# mainboard.net
KiCad netlist of a schematic drawn in EAGLE
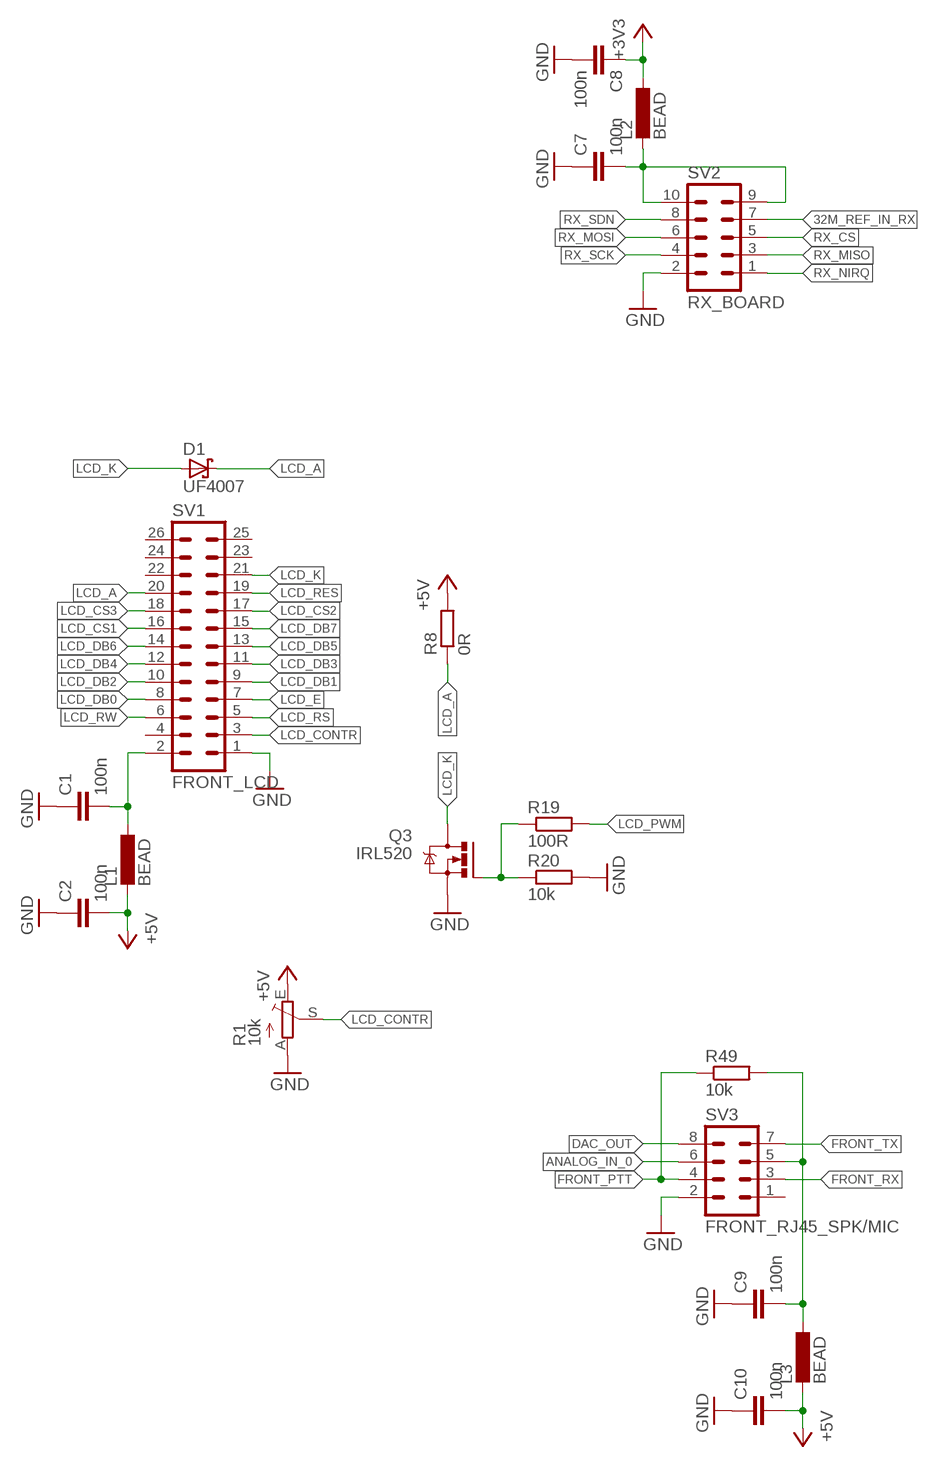
[diagram p0: schematic, sheet 1, part 1 of 3]
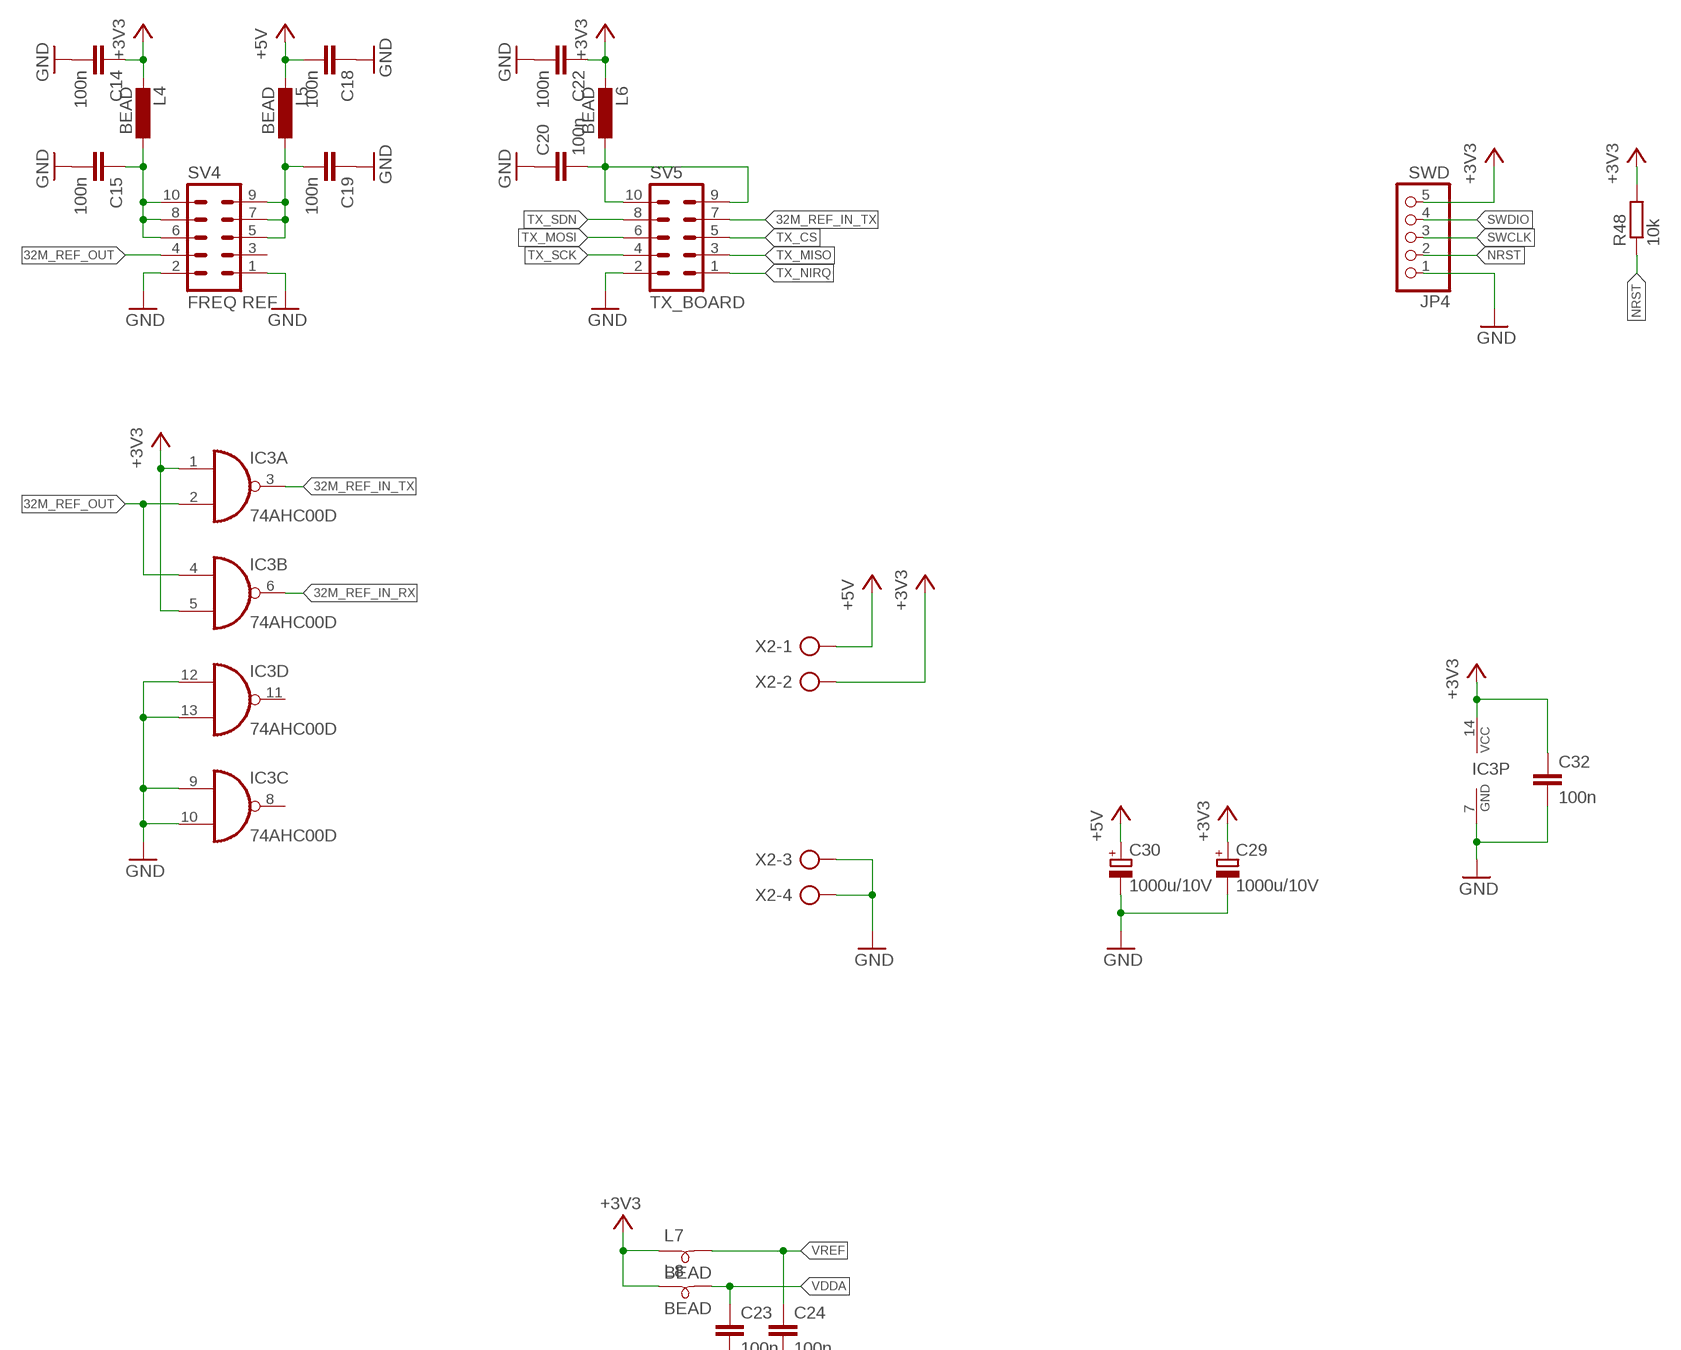
[diagram p1: schematic, sheet 1, part 2 of 3]
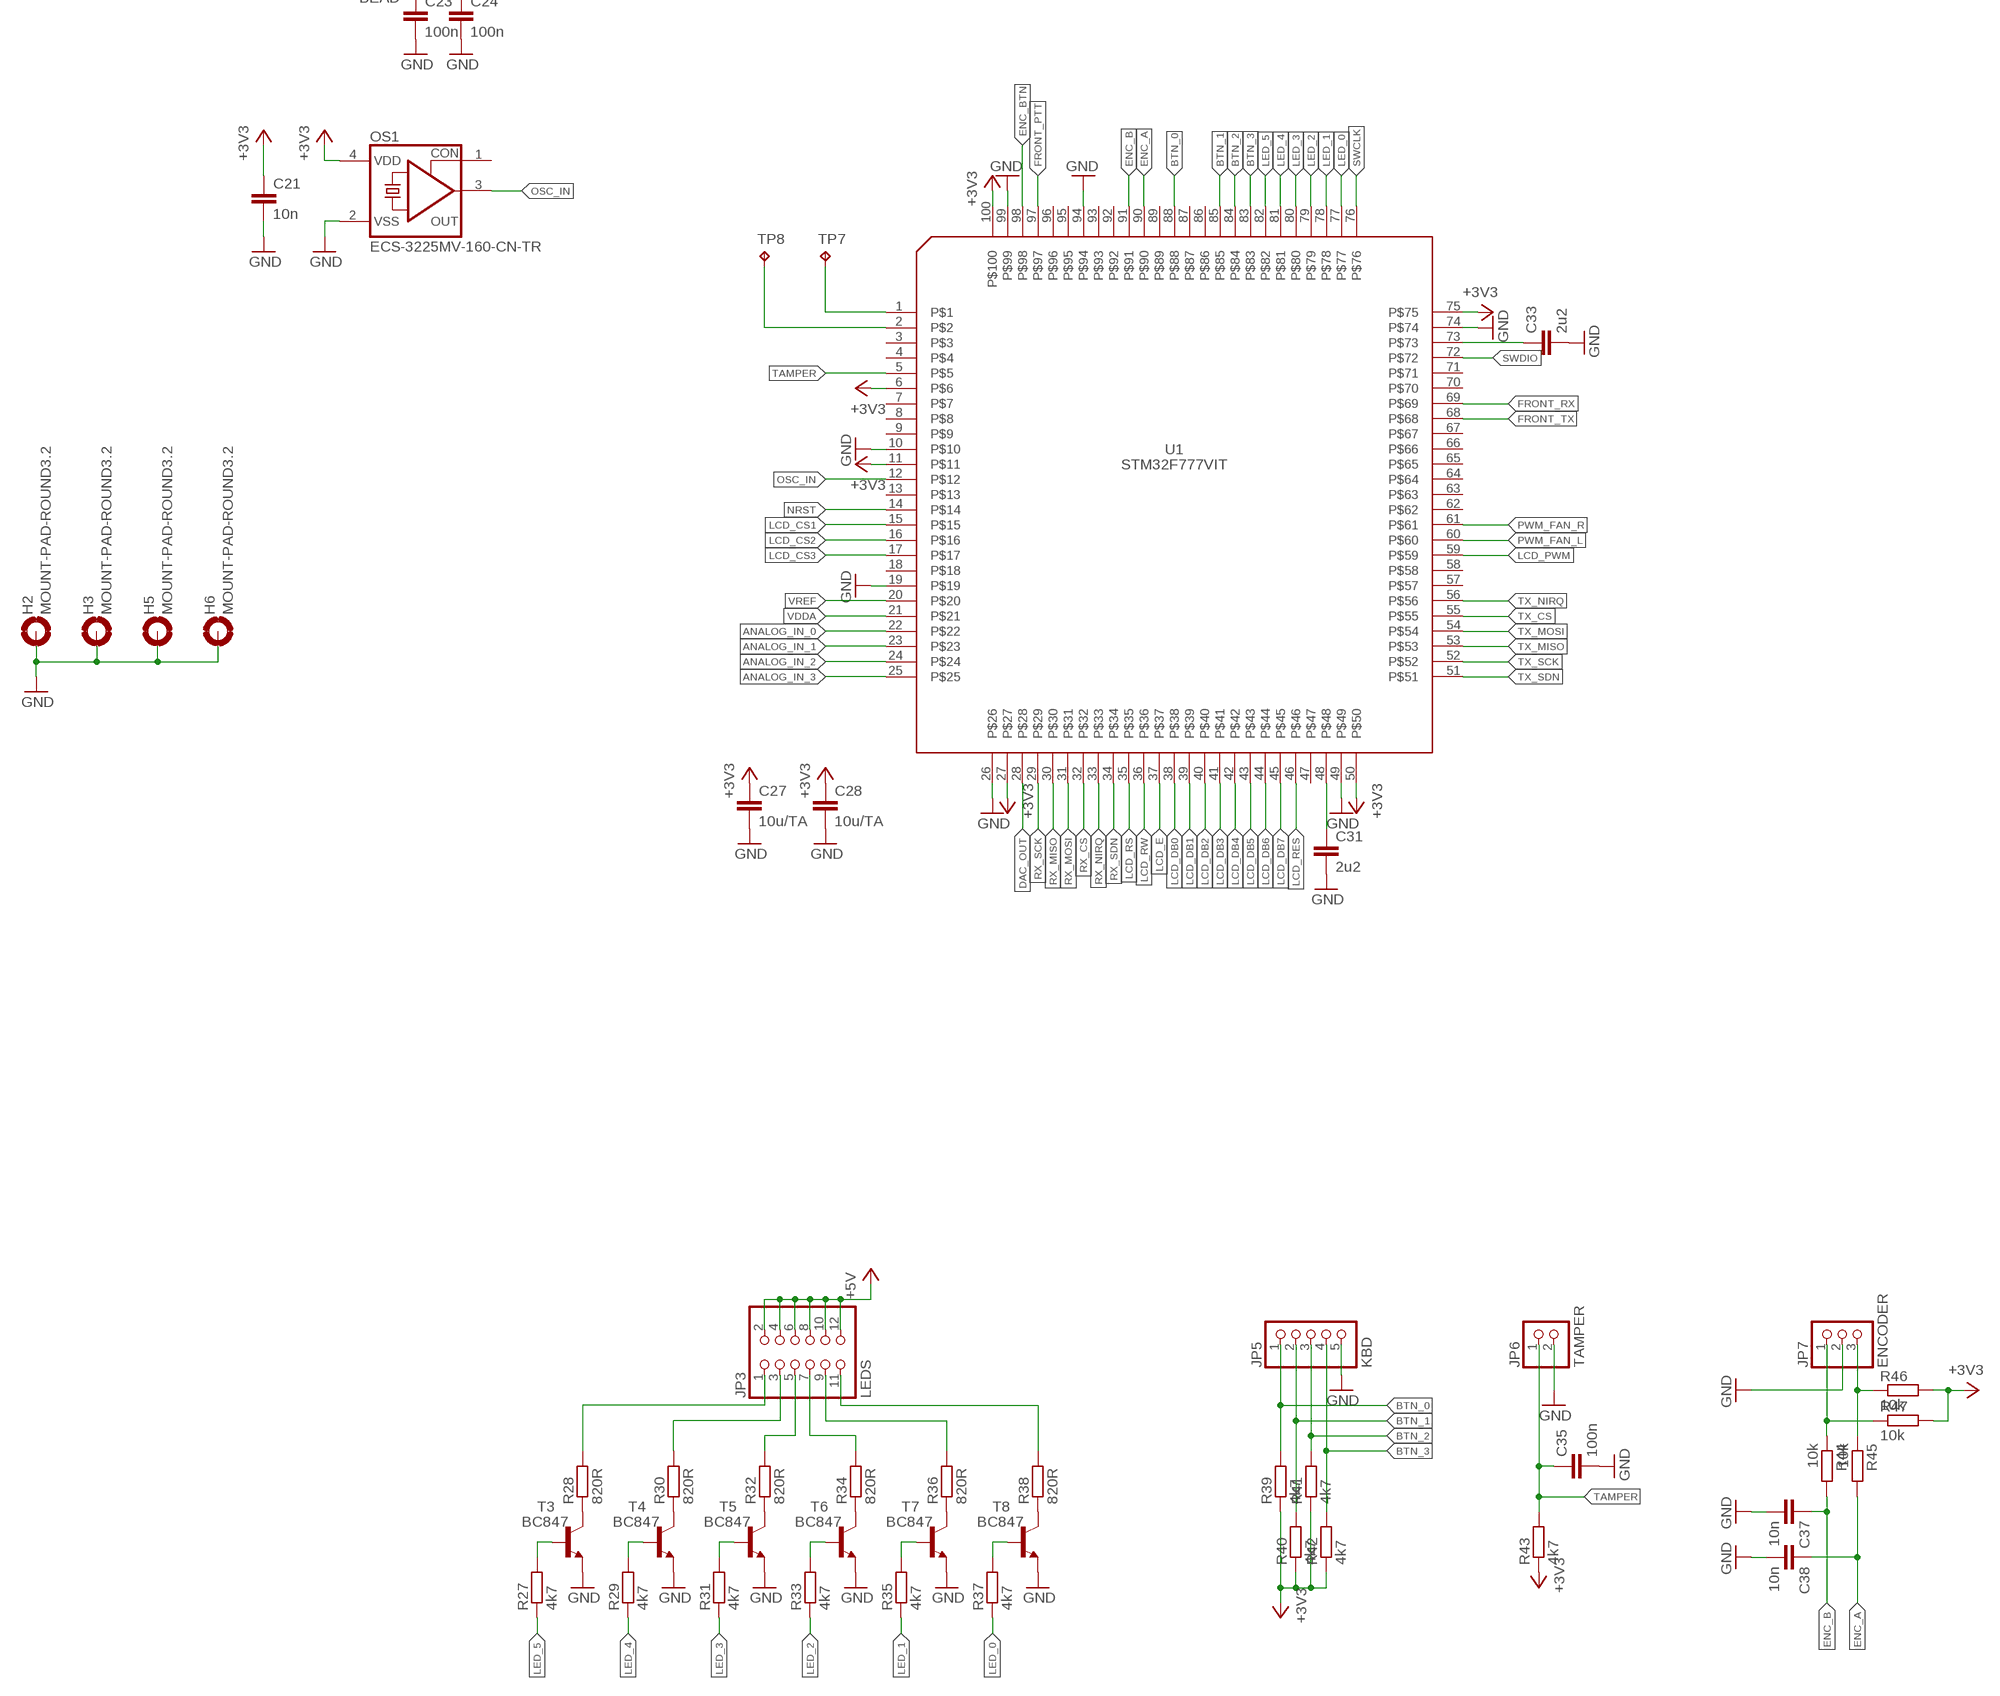
[diagram p2: schematic, sheet 1, part 3 of 3]

(export (version "E")
  (design (tool "Eeschema 10.0.6"))
  (components
    (comp (ref "C1")
      (value "100n")
      (footprint "eagle-import:C0805")
      (libsource (lib "eagle-import") (part "C-EUC0805"))
    )
    (comp (ref "C2")
      (value "100n")
      (footprint "eagle-import:C0805")
      (libsource (lib "eagle-import") (part "C-EUC0805"))
    )
    (comp (ref "C7")
      (value "100n")
      (footprint "eagle-import:C0805")
      (libsource (lib "eagle-import") (part "C-EUC0805"))
    )
    (comp (ref "C8")
      (value "100n")
      (footprint "eagle-import:C0805")
      (libsource (lib "eagle-import") (part "C-EUC0805"))
    )
    (comp (ref "C9")
      (value "100n")
      (footprint "eagle-import:C0805")
      (libsource (lib "eagle-import") (part "C-EUC0805"))
    )
    (comp (ref "C10")
      (value "100n")
      (footprint "eagle-import:C0805")
      (libsource (lib "eagle-import") (part "C-EUC0805"))
    )
    (comp (ref "C14")
      (value "100n")
      (footprint "eagle-import:C0805")
      (libsource (lib "eagle-import") (part "C-EUC0805"))
    )
    (comp (ref "C15")
      (value "100n")
      (footprint "eagle-import:C0805")
      (libsource (lib "eagle-import") (part "C-EUC0805"))
    )
    (comp (ref "C18")
      (value "100n")
      (footprint "eagle-import:C0805")
      (libsource (lib "eagle-import") (part "C-EUC0805"))
    )
    (comp (ref "C19")
      (value "100n")
      (footprint "eagle-import:C0805")
      (libsource (lib "eagle-import") (part "C-EUC0805"))
    )
    (comp (ref "C20")
      (value "100n")
      (footprint "eagle-import:C0805")
      (libsource (lib "eagle-import") (part "C-EUC0805"))
    )
    (comp (ref "C21")
      (value "10n")
      (footprint "eagle-import:C0805")
      (libsource (lib "eagle-import") (part "C-EUC0805"))
    )
    (comp (ref "C22")
      (value "100n")
      (footprint "eagle-import:C0805")
      (libsource (lib "eagle-import") (part "C-EUC0805"))
    )
    (comp (ref "C23")
      (value "100n")
      (footprint "eagle-import:C0805")
      (libsource (lib "eagle-import") (part "C-EUC0805"))
    )
    (comp (ref "C24")
      (value "100n")
      (footprint "eagle-import:C0805")
      (libsource (lib "eagle-import") (part "C-EUC0805"))
    )
    (comp (ref "C27")
      (value "10u/TA")
      (footprint "eagle-import:C1206")
      (libsource (lib "eagle-import") (part "resistor_C-EUC1206"))
    )
    (comp (ref "C28")
      (value "10u/TA")
      (footprint "eagle-import:C1206")
      (libsource (lib "eagle-import") (part "resistor_C-EUC1206"))
    )
    (comp (ref "C29")
      (value "1000u/10V")
      (footprint "eagle-import:E3,5-8")
      (libsource (lib "eagle-import") (part "CPOL-EUE3.5-8"))
    )
    (comp (ref "C30")
      (value "1000u/10V")
      (footprint "eagle-import:E3,5-8")
      (libsource (lib "eagle-import") (part "CPOL-EUE3.5-8"))
    )
    (comp (ref "C31")
      (value "2u2")
      (footprint "eagle-import:C0805")
      (libsource (lib "eagle-import") (part "C-EUC0805"))
    )
    (comp (ref "C32")
      (value "100n")
      (footprint "eagle-import:C0805")
      (libsource (lib "eagle-import") (part "C-EUC0805"))
    )
    (comp (ref "C33")
      (value "2u2")
      (footprint "eagle-import:C0805")
      (libsource (lib "eagle-import") (part "C-EUC0805"))
    )
    (comp (ref "C35")
      (value "100n")
      (footprint "eagle-import:C0805")
      (libsource (lib "eagle-import") (part "C-EUC0805"))
    )
    (comp (ref "C37")
      (value "10n")
      (footprint "eagle-import:C0805")
      (libsource (lib "eagle-import") (part "C-EUC0805"))
    )
    (comp (ref "C38")
      (value "10n")
      (footprint "eagle-import:C0805")
      (libsource (lib "eagle-import") (part "C-EUC0805"))
    )
    (comp (ref "D1")
      (value "UF4007")
      (footprint "eagle-import:DO41-7.6")
      (libsource (lib "eagle-import") (part "1N5819-T"))
    )
    (comp (ref "H2")
      (value "MOUNT-PAD-ROUND3.2")
      (footprint "eagle-import:3,2-PAD")
      (libsource (lib "eagle-import") (part "MOUNT-PAD-ROUND3.2"))
    )
    (comp (ref "H3")
      (value "MOUNT-PAD-ROUND3.2")
      (footprint "eagle-import:3,2-PAD")
      (libsource (lib "eagle-import") (part "MOUNT-PAD-ROUND3.2"))
    )
    (comp (ref "H5")
      (value "MOUNT-PAD-ROUND3.2")
      (footprint "eagle-import:3,2-PAD")
      (libsource (lib "eagle-import") (part "MOUNT-PAD-ROUND3.2"))
    )
    (comp (ref "H6")
      (value "MOUNT-PAD-ROUND3.2")
      (footprint "eagle-import:3,2-PAD")
      (libsource (lib "eagle-import") (part "MOUNT-PAD-ROUND3.2"))
    )
    (comp (ref "IC3")
      (value "74AHC00D")
      (footprint "eagle-import:SO14")
      (libsource (lib "eagle-import") (part "7400D"))
    )
    (comp (ref "JP3")
      (value "LEDS")
      (footprint "eagle-import:2X06")
      (libsource (lib "eagle-import") (part "PINHD-2X6"))
    )
    (comp (ref "JP4")
      (value "SWD")
      (footprint "eagle-import:1X05")
      (libsource (lib "eagle-import") (part "PINHD-1X5"))
    )
    (comp (ref "JP5")
      (value "KBD")
      (footprint "eagle-import:1X05")
      (libsource (lib "eagle-import") (part "PINHD-1X5"))
    )
    (comp (ref "JP6")
      (value "TAMPER")
      (footprint "eagle-import:1X02")
      (libsource (lib "eagle-import") (part "PINHD-1X2"))
    )
    (comp (ref "JP7")
      (value "ENCODER")
      (footprint "eagle-import:1X03")
      (libsource (lib "eagle-import") (part "PINHD-1X3"))
    )
    (comp (ref "L1")
      (value "BEAD")
      (footprint "eagle-import:0204_7")
      (libsource (lib "eagle-import") (part "L-EU0204/7"))
    )
    (comp (ref "L2")
      (value "BEAD")
      (footprint "eagle-import:0204_7")
      (libsource (lib "eagle-import") (part "L-EU0204/7"))
    )
    (comp (ref "L3")
      (value "BEAD")
      (footprint "eagle-import:0204_7")
      (libsource (lib "eagle-import") (part "L-EU0204/7"))
    )
    (comp (ref "L4")
      (value "BEAD")
      (footprint "eagle-import:0204_7")
      (libsource (lib "eagle-import") (part "L-EU0204/7"))
    )
    (comp (ref "L5")
      (value "BEAD")
      (footprint "eagle-import:0204_7")
      (libsource (lib "eagle-import") (part "L-EU0204/7"))
    )
    (comp (ref "L6")
      (value "BEAD")
      (footprint "eagle-import:0204_7")
      (libsource (lib "eagle-import") (part "L-EU0204/7"))
    )
    (comp (ref "L7")
      (value "BEAD")
      (footprint "eagle-import:SM-B5")
      (libsource (lib "eagle-import") (part "SM-B5"))
    )
    (comp (ref "L8")
      (value "BEAD")
      (footprint "eagle-import:SM-B5")
      (libsource (lib "eagle-import") (part "SM-B5"))
    )
    (comp (ref "OS1")
      (value "ECS-3225MV-160-CN-TR")
      (footprint "eagle-import:3.4X2.7-4-PAD")
      (libsource (lib "eagle-import") (part "OSC-OE-CFPS-39"))
    )
    (comp (ref "Q3")
      (value "IRL520")
      (footprint "eagle-import:TO220BV")
      (libsource (lib "eagle-import") (part "IRF540"))
    )
    (comp (ref "R1")
      (value "10k")
      (footprint "eagle-import:CA6V")
      (libsource (lib "eagle-import") (part "TRIM_EU-CA6V"))
    )
    (comp (ref "R8")
      (value "0R")
      (footprint "eagle-import:R1206")
      (libsource (lib "eagle-import") (part "R-EU_R1206"))
    )
    (comp (ref "R19")
      (value "100R")
      (footprint "eagle-import:R0805")
      (libsource (lib "eagle-import") (part "resistor_R-EU_R0805"))
    )
    (comp (ref "R20")
      (value "10k")
      (footprint "eagle-import:R0805")
      (libsource (lib "eagle-import") (part "resistor_R-EU_R0805"))
    )
    (comp (ref "R27")
      (value "4k7")
      (footprint "eagle-import:R0805")
      (libsource (lib "eagle-import") (part "resistor_R-EU_R0805"))
    )
    (comp (ref "R28")
      (value "820R")
      (footprint "eagle-import:R0805")
      (libsource (lib "eagle-import") (part "resistor_R-EU_R0805"))
    )
    (comp (ref "R29")
      (value "4k7")
      (footprint "eagle-import:R0805")
      (libsource (lib "eagle-import") (part "resistor_R-EU_R0805"))
    )
    (comp (ref "R30")
      (value "820R")
      (footprint "eagle-import:R0805")
      (libsource (lib "eagle-import") (part "resistor_R-EU_R0805"))
    )
    (comp (ref "R31")
      (value "4k7")
      (footprint "eagle-import:R0805")
      (libsource (lib "eagle-import") (part "resistor_R-EU_R0805"))
    )
    (comp (ref "R32")
      (value "820R")
      (footprint "eagle-import:R0805")
      (libsource (lib "eagle-import") (part "resistor_R-EU_R0805"))
    )
    (comp (ref "R33")
      (value "4k7")
      (footprint "eagle-import:R0805")
      (libsource (lib "eagle-import") (part "resistor_R-EU_R0805"))
    )
    (comp (ref "R34")
      (value "820R")
      (footprint "eagle-import:R0805")
      (libsource (lib "eagle-import") (part "resistor_R-EU_R0805"))
    )
    (comp (ref "R35")
      (value "4k7")
      (footprint "eagle-import:R0805")
      (libsource (lib "eagle-import") (part "resistor_R-EU_R0805"))
    )
    (comp (ref "R36")
      (value "820R")
      (footprint "eagle-import:R0805")
      (libsource (lib "eagle-import") (part "resistor_R-EU_R0805"))
    )
    (comp (ref "R37")
      (value "4k7")
      (footprint "eagle-import:R0805")
      (libsource (lib "eagle-import") (part "resistor_R-EU_R0805"))
    )
    (comp (ref "R38")
      (value "820R")
      (footprint "eagle-import:R0805")
      (libsource (lib "eagle-import") (part "resistor_R-EU_R0805"))
    )
    (comp (ref "R39")
      (value "4k7")
      (footprint "eagle-import:R0805")
      (libsource (lib "eagle-import") (part "resistor_R-EU_R0805"))
    )
    (comp (ref "R40")
      (value "4k7")
      (footprint "eagle-import:R0805")
      (libsource (lib "eagle-import") (part "resistor_R-EU_R0805"))
    )
    (comp (ref "R41")
      (value "4k7")
      (footprint "eagle-import:R0805")
      (libsource (lib "eagle-import") (part "resistor_R-EU_R0805"))
    )
    (comp (ref "R42")
      (value "4k7")
      (footprint "eagle-import:R0805")
      (libsource (lib "eagle-import") (part "resistor_R-EU_R0805"))
    )
    (comp (ref "R43")
      (value "4k7")
      (footprint "eagle-import:R0805")
      (libsource (lib "eagle-import") (part "resistor_R-EU_R0805"))
    )
    (comp (ref "R44")
      (value "10k")
      (footprint "eagle-import:R0805")
      (libsource (lib "eagle-import") (part "R-EU_R0805"))
    )
    (comp (ref "R45")
      (value "10k")
      (footprint "eagle-import:R0805")
      (libsource (lib "eagle-import") (part "R-EU_R0805"))
    )
    (comp (ref "R46")
      (value "10k")
      (footprint "eagle-import:R0805")
      (libsource (lib "eagle-import") (part "R-EU_R0805"))
    )
    (comp (ref "R47")
      (value "10k")
      (footprint "eagle-import:R0805")
      (libsource (lib "eagle-import") (part "R-EU_R0805"))
    )
    (comp (ref "R48")
      (value "10k")
      (footprint "eagle-import:R0805")
      (libsource (lib "eagle-import") (part "resistor_R-EU_R0805"))
    )
    (comp (ref "R49")
      (value "10k")
      (footprint "eagle-import:R0805")
      (libsource (lib "eagle-import") (part "resistor_R-EU_R0805"))
    )
    (comp (ref "SV1")
      (value "FRONT_LCD")
      (footprint "eagle-import:ML26")
      (libsource (lib "eagle-import") (part "ML26"))
    )
    (comp (ref "SV2")
      (value "RX_BOARD")
      (footprint "eagle-import:ML10")
      (libsource (lib "eagle-import") (part "ML10"))
    )
    (comp (ref "SV3")
      (value "FRONT_RJ45_SPK/MIC")
      (footprint "eagle-import:MA04-2")
      (libsource (lib "eagle-import") (part "MA04-2"))
    )
    (comp (ref "SV4")
      (value "FREQ REF")
      (footprint "eagle-import:ML10")
      (libsource (lib "eagle-import") (part "ML10"))
    )
    (comp (ref "SV5")
      (value "TX_BOARD")
      (footprint "eagle-import:ML10")
      (libsource (lib "eagle-import") (part "ML10"))
    )
    (comp (ref "T3")
      (value "BC847")
      (footprint "eagle-import:SOT23")
      (libsource (lib "eagle-import") (part "BC847"))
    )
    (comp (ref "T4")
      (value "BC847")
      (footprint "eagle-import:SOT23")
      (libsource (lib "eagle-import") (part "BC847"))
    )
    (comp (ref "T5")
      (value "BC847")
      (footprint "eagle-import:SOT23")
      (libsource (lib "eagle-import") (part "BC847"))
    )
    (comp (ref "T6")
      (value "BC847")
      (footprint "eagle-import:SOT23")
      (libsource (lib "eagle-import") (part "BC847"))
    )
    (comp (ref "T7")
      (value "BC847")
      (footprint "eagle-import:SOT23")
      (libsource (lib "eagle-import") (part "BC847"))
    )
    (comp (ref "T8")
      (value "BC847")
      (footprint "eagle-import:SOT23")
      (libsource (lib "eagle-import") (part "BC847"))
    )
    (comp (ref "TP7")
      (value "TPB2,54")
      (footprint "eagle-import:B2,54")
      (libsource (lib "eagle-import") (part "TPB2,54"))
    )
    (comp (ref "TP8")
      (value "TPB2,54")
      (footprint "eagle-import:B2,54")
      (libsource (lib "eagle-import") (part "TPB2,54"))
    )
    (comp (ref "U1")
      (value "STM32F777VIT")
      (footprint "eagle-import:LQFP100")
      (libsource (lib "eagle-import") (part "STM32F777VIT"))
    )
    (comp (ref "X2")
      (value "AK500/4")
      (footprint "eagle-import:AK500_4")
      (libsource (lib "eagle-import") (part "AK500/4"))
    )
  )
  (nets
    (net (code "1") (name "+3V3") (class "Default")
      (node (ref "C14") (pin "1") (pinfunction "1_1") (pintype "passive"))
      (node (ref "C21") (pin "1") (pinfunction "1_1") (pintype "passive"))
      (node (ref "C22") (pin "1") (pinfunction "1_1") (pintype "passive"))
      (node (ref "C27") (pin "1") (pinfunction "1_1") (pintype "passive"))
      (node (ref "C28") (pin "1") (pinfunction "1_1") (pintype "passive"))
      (node (ref "C29") (pin "+") (pinfunction "+_+") (pintype "passive"))
      (node (ref "C32") (pin "1") (pinfunction "1_1") (pintype "passive"))
      (node (ref "C8") (pin "1") (pinfunction "1_1") (pintype "passive"))
      (node (ref "IC3") (pin "1") (pinfunction "I0_1") (pintype "input"))
      (node (ref "IC3") (pin "14") (pinfunction "VCC_14") (pintype "power_in"))
      (node (ref "IC3") (pin "5") (pinfunction "I1_5") (pintype "input"))
      (node (ref "JP4") (pin "5") (pinfunction "5_5") (pintype "passive"))
      (node (ref "L2") (pin "1") (pinfunction "1_1") (pintype "passive"))
      (node (ref "L4") (pin "2") (pinfunction "2_2") (pintype "passive"))
      (node (ref "L6") (pin "2") (pinfunction "2_2") (pintype "passive"))
      (node (ref "L7") (pin "1") (pinfunction "1_1") (pintype "passive"))
      (node (ref "L8") (pin "1") (pinfunction "1_1") (pintype "passive"))
      (node (ref "OS1") (pin "4") (pinfunction "VDD_4") (pintype "power_in"))
      (node (ref "R39") (pin "1") (pinfunction "1_1") (pintype "passive"))
      (node (ref "R40") (pin "1") (pinfunction "1_1") (pintype "passive"))
      (node (ref "R41") (pin "1") (pinfunction "1_1") (pintype "passive"))
      (node (ref "R42") (pin "1") (pinfunction "1_1") (pintype "passive"))
      (node (ref "R43") (pin "1") (pinfunction "1_1") (pintype "passive"))
      (node (ref "R46") (pin "2") (pinfunction "2_2") (pintype "passive"))
      (node (ref "R47") (pin "2") (pinfunction "2_2") (pintype "passive"))
      (node (ref "R48") (pin "2") (pinfunction "2_2") (pintype "passive"))
      (node (ref "U1") (pin "100") (pinfunction "P$100_100") (pintype "bidirectional"))
      (node (ref "U1") (pin "11") (pinfunction "P$11_11") (pintype "bidirectional"))
      (node (ref "U1") (pin "27") (pinfunction "P$27_27") (pintype "bidirectional"))
      (node (ref "U1") (pin "50") (pinfunction "P$50_50") (pintype "bidirectional"))
      (node (ref "U1") (pin "6") (pinfunction "P$6_6") (pintype "bidirectional"))
      (node (ref "U1") (pin "75") (pinfunction "P$75_75") (pintype "bidirectional"))
      (node (ref "X2") (pin "2") (pinfunction "KL_2") (pintype "passive"))
    )
    (net (code "2") (name "+5V") (class "Default")
      (node (ref "C10") (pin "2") (pinfunction "2_2") (pintype "passive"))
      (node (ref "C18") (pin "2") (pinfunction "2_2") (pintype "passive"))
      (node (ref "C2") (pin "2") (pinfunction "2_2") (pintype "passive"))
      (node (ref "C30") (pin "+") (pinfunction "+_+") (pintype "passive"))
      (node (ref "JP3") (pin "10") (pinfunction "10_10") (pintype "passive"))
      (node (ref "JP3") (pin "12") (pinfunction "12_12") (pintype "passive"))
      (node (ref "JP3") (pin "2") (pinfunction "2_2") (pintype "passive"))
      (node (ref "JP3") (pin "4") (pinfunction "4_4") (pintype "passive"))
      (node (ref "JP3") (pin "6") (pinfunction "6_6") (pintype "passive"))
      (node (ref "JP3") (pin "8") (pinfunction "8_8") (pintype "passive"))
      (node (ref "L1") (pin "2") (pinfunction "2_2") (pintype "passive"))
      (node (ref "L3") (pin "2") (pinfunction "2_2") (pintype "passive"))
      (node (ref "L5") (pin "2") (pinfunction "2_2") (pintype "passive"))
      (node (ref "R1") (pin "E") (pinfunction "E_E") (pintype "passive"))
      (node (ref "R8") (pin "2") (pinfunction "2_2") (pintype "passive"))
      (node (ref "X2") (pin "1") (pinfunction "KL_1") (pintype "passive"))
    )
    (net (code "3") (name "32M_REF_IN_RX") (class "Default")
      (node (ref "IC3") (pin "6") (pinfunction "O_6") (pintype "output"))
      (node (ref "SV2") (pin "7") (pinfunction "7_7") (pintype "passive"))
    )
    (net (code "4") (name "32M_REF_IN_TX") (class "Default")
      (node (ref "IC3") (pin "3") (pinfunction "O_3") (pintype "output"))
      (node (ref "SV5") (pin "7") (pinfunction "7_7") (pintype "passive"))
    )
    (net (code "5") (name "32M_REF_OUT") (class "Default")
      (node (ref "IC3") (pin "2") (pinfunction "I1_2") (pintype "input"))
      (node (ref "IC3") (pin "4") (pinfunction "I0_4") (pintype "input"))
      (node (ref "SV4") (pin "4") (pinfunction "4_4") (pintype "passive"))
    )
    (net (code "6") (name "ANALOG_IN_0") (class "Default")
      (node (ref "SV3") (pin "6") (pinfunction "6_6") (pintype "passive"))
      (node (ref "U1") (pin "22") (pinfunction "P$22_22") (pintype "bidirectional"))
    )
    (net (code "7") (name "ANALOG_IN_1") (class "Default")
      (node (ref "U1") (pin "23") (pinfunction "P$23_23") (pintype "bidirectional"))
    )
    (net (code "8") (name "ANALOG_IN_2") (class "Default")
      (node (ref "U1") (pin "24") (pinfunction "P$24_24") (pintype "bidirectional"))
    )
    (net (code "9") (name "ANALOG_IN_3") (class "Default")
      (node (ref "U1") (pin "25") (pinfunction "P$25_25") (pintype "bidirectional"))
    )
    (net (code "10") (name "BTN_0") (class "Default")
      (node (ref "JP5") (pin "1") (pinfunction "1_1") (pintype "passive"))
      (node (ref "R39") (pin "2") (pinfunction "2_2") (pintype "passive"))
      (node (ref "U1") (pin "88") (pinfunction "P$88_88") (pintype "bidirectional"))
    )
    (net (code "11") (name "BTN_1") (class "Default")
      (node (ref "JP5") (pin "2") (pinfunction "2_2") (pintype "passive"))
      (node (ref "R40") (pin "2") (pinfunction "2_2") (pintype "passive"))
      (node (ref "U1") (pin "85") (pinfunction "P$85_85") (pintype "bidirectional"))
    )
    (net (code "12") (name "BTN_2") (class "Default")
      (node (ref "JP5") (pin "3") (pinfunction "3_3") (pintype "passive"))
      (node (ref "R41") (pin "2") (pinfunction "2_2") (pintype "passive"))
      (node (ref "U1") (pin "84") (pinfunction "P$84_84") (pintype "bidirectional"))
    )
    (net (code "13") (name "BTN_3") (class "Default")
      (node (ref "JP5") (pin "4") (pinfunction "4_4") (pintype "passive"))
      (node (ref "R42") (pin "2") (pinfunction "2_2") (pintype "passive"))
      (node (ref "U1") (pin "83") (pinfunction "P$83_83") (pintype "bidirectional"))
    )
    (net (code "14") (name "DAC_OUT") (class "Default")
      (node (ref "SV3") (pin "8") (pinfunction "8_8") (pintype "passive"))
      (node (ref "U1") (pin "28") (pinfunction "P$28_28") (pintype "bidirectional"))
    )
    (net (code "15") (name "ENC_A") (class "Default")
      (node (ref "C38") (pin "1") (pinfunction "1_1") (pintype "passive"))
      (node (ref "R45") (pin "2") (pinfunction "2_2") (pintype "passive"))
      (node (ref "U1") (pin "90") (pinfunction "P$90_90") (pintype "bidirectional"))
    )
    (net (code "16") (name "ENC_B") (class "Default")
      (node (ref "C37") (pin "1") (pinfunction "1_1") (pintype "passive"))
      (node (ref "R44") (pin "2") (pinfunction "2_2") (pintype "passive"))
      (node (ref "U1") (pin "91") (pinfunction "P$91_91") (pintype "bidirectional"))
    )
    (net (code "17") (name "ENC_BTN") (class "Default")
      (node (ref "U1") (pin "98") (pinfunction "P$98_98") (pintype "bidirectional"))
    )
    (net (code "18") (name "FRONT_PTT") (class "Default")
      (node (ref "R49") (pin "1") (pinfunction "1_1") (pintype "passive"))
      (node (ref "SV3") (pin "4") (pinfunction "4_4") (pintype "passive"))
      (node (ref "U1") (pin "97") (pinfunction "P$97_97") (pintype "bidirectional"))
    )
    (net (code "19") (name "FRONT_RX") (class "Default")
      (node (ref "SV3") (pin "3") (pinfunction "3_3") (pintype "passive"))
      (node (ref "U1") (pin "69") (pinfunction "P$69_69") (pintype "bidirectional"))
    )
    (net (code "20") (name "FRONT_TX") (class "Default")
      (node (ref "SV3") (pin "7") (pinfunction "7_7") (pintype "passive"))
      (node (ref "U1") (pin "68") (pinfunction "P$68_68") (pintype "bidirectional"))
    )
    (net (code "21") (name "GND") (class "Default")
      (node (ref "C1") (pin "1") (pinfunction "1_1") (pintype "passive"))
      (node (ref "C10") (pin "1") (pinfunction "1_1") (pintype "passive"))
      (node (ref "C14") (pin "2") (pinfunction "2_2") (pintype "passive"))
      (node (ref "C15") (pin "2") (pinfunction "2_2") (pintype "passive"))
      (node (ref "C18") (pin "1") (pinfunction "1_1") (pintype "passive"))
      (node (ref "C19") (pin "1") (pinfunction "1_1") (pintype "passive"))
      (node (ref "C2") (pin "1") (pinfunction "1_1") (pintype "passive"))
      (node (ref "C20") (pin "1") (pinfunction "1_1") (pintype "passive"))
      (node (ref "C21") (pin "2") (pinfunction "2_2") (pintype "passive"))
      (node (ref "C22") (pin "2") (pinfunction "2_2") (pintype "passive"))
      (node (ref "C23") (pin "2") (pinfunction "2_2") (pintype "passive"))
      (node (ref "C24") (pin "2") (pinfunction "2_2") (pintype "passive"))
      (node (ref "C27") (pin "2") (pinfunction "2_2") (pintype "passive"))
      (node (ref "C28") (pin "2") (pinfunction "2_2") (pintype "passive"))
      (node (ref "C29") (pin "-") (pinfunction "-_-") (pintype "passive"))
      (node (ref "C30") (pin "-") (pinfunction "-_-") (pintype "passive"))
      (node (ref "C31") (pin "2") (pinfunction "2_2") (pintype "passive"))
      (node (ref "C32") (pin "2") (pinfunction "2_2") (pintype "passive"))
      (node (ref "C33") (pin "2") (pinfunction "2_2") (pintype "passive"))
      (node (ref "C35") (pin "2") (pinfunction "2_2") (pintype "passive"))
      (node (ref "C37") (pin "2") (pinfunction "2_2") (pintype "passive"))
      (node (ref "C38") (pin "2") (pinfunction "2_2") (pintype "passive"))
      (node (ref "C7") (pin "1") (pinfunction "1_1") (pintype "passive"))
      (node (ref "C8") (pin "2") (pinfunction "2_2") (pintype "passive"))
      (node (ref "C9") (pin "1") (pinfunction "1_1") (pintype "passive"))
      (node (ref "H2") (pin "B3,2") (pinfunction "MOUNT_B3,2") (pintype "passive"))
      (node (ref "H3") (pin "B3,2") (pinfunction "MOUNT_B3,2") (pintype "passive"))
      (node (ref "H5") (pin "B3,2") (pinfunction "MOUNT_B3,2") (pintype "passive"))
      (node (ref "H6") (pin "B3,2") (pinfunction "MOUNT_B3,2") (pintype "passive"))
      (node (ref "IC3") (pin "10") (pinfunction "I1_10") (pintype "input"))
      (node (ref "IC3") (pin "12") (pinfunction "I0_12") (pintype "input"))
      (node (ref "IC3") (pin "13") (pinfunction "I1_13") (pintype "input"))
      (node (ref "IC3") (pin "7") (pinfunction "GND_7") (pintype "power_in"))
      (node (ref "IC3") (pin "9") (pinfunction "I0_9") (pintype "input"))
      (node (ref "JP4") (pin "1") (pinfunction "1_1") (pintype "passive"))
      (node (ref "JP5") (pin "5") (pinfunction "5_5") (pintype "passive"))
      (node (ref "JP6") (pin "2") (pinfunction "2_2") (pintype "passive"))
      (node (ref "JP7") (pin "2") (pinfunction "2_2") (pintype "passive"))
      (node (ref "OS1") (pin "2") (pinfunction "VSS_2") (pintype "power_in"))
      (node (ref "Q3") (pin "S") (pinfunction "S_S") (pintype "passive"))
      (node (ref "R1") (pin "A") (pinfunction "A_A") (pintype "passive"))
      (node (ref "R20") (pin "2") (pinfunction "2_2") (pintype "passive"))
      (node (ref "SV1") (pin "1") (pinfunction "1_1") (pintype "passive"))
      (node (ref "SV2") (pin "2") (pinfunction "2_2") (pintype "passive"))
      (node (ref "SV3") (pin "2") (pinfunction "2_2") (pintype "passive"))
      (node (ref "SV4") (pin "1") (pinfunction "1_1") (pintype "passive"))
      (node (ref "SV4") (pin "2") (pinfunction "2_2") (pintype "passive"))
      (node (ref "SV5") (pin "2") (pinfunction "2_2") (pintype "passive"))
      (node (ref "T3") (pin "2") (pinfunction "E_2") (pintype "passive"))
      (node (ref "T4") (pin "2") (pinfunction "E_2") (pintype "passive"))
      (node (ref "T5") (pin "2") (pinfunction "E_2") (pintype "passive"))
      (node (ref "T6") (pin "2") (pinfunction "E_2") (pintype "passive"))
      (node (ref "T7") (pin "2") (pinfunction "E_2") (pintype "passive"))
      (node (ref "T8") (pin "2") (pinfunction "E_2") (pintype "passive"))
      (node (ref "U1") (pin "10") (pinfunction "P$10_10") (pintype "bidirectional"))
      (node (ref "U1") (pin "19") (pinfunction "P$19_19") (pintype "bidirectional"))
      (node (ref "U1") (pin "26") (pinfunction "P$26_26") (pintype "bidirectional"))
      (node (ref "U1") (pin "49") (pinfunction "P$49_49") (pintype "bidirectional"))
      (node (ref "U1") (pin "74") (pinfunction "P$74_74") (pintype "bidirectional"))
      (node (ref "U1") (pin "94") (pinfunction "P$94_94") (pintype "bidirectional"))
      (node (ref "U1") (pin "99") (pinfunction "P$99_99") (pintype "bidirectional"))
      (node (ref "X2") (pin "3") (pinfunction "KL_3") (pintype "passive"))
      (node (ref "X2") (pin "4") (pinfunction "KL_4") (pintype "passive"))
    )
    (net (code "22") (name "LCD_A") (class "Default")
      (node (ref "D1") (pin "C") (pinfunction "C_C") (pintype "passive"))
      (node (ref "R8") (pin "1") (pinfunction "1_1") (pintype "passive"))
      (node (ref "SV1") (pin "20") (pinfunction "20_20") (pintype "passive"))
    )
    (net (code "23") (name "LCD_CONTR") (class "Default")
      (node (ref "R1") (pin "S") (pinfunction "S_S") (pintype "passive"))
      (node (ref "SV1") (pin "3") (pinfunction "3_3") (pintype "passive"))
    )
    (net (code "24") (name "LCD_CS1") (class "Default")
      (node (ref "SV1") (pin "16") (pinfunction "16_16") (pintype "passive"))
      (node (ref "U1") (pin "15") (pinfunction "P$15_15") (pintype "bidirectional"))
    )
    (net (code "25") (name "LCD_CS2") (class "Default")
      (node (ref "SV1") (pin "17") (pinfunction "17_17") (pintype "passive"))
      (node (ref "U1") (pin "16") (pinfunction "P$16_16") (pintype "bidirectional"))
    )
    (net (code "26") (name "LCD_CS3") (class "Default")
      (node (ref "SV1") (pin "18") (pinfunction "18_18") (pintype "passive"))
      (node (ref "U1") (pin "17") (pinfunction "P$17_17") (pintype "bidirectional"))
    )
    (net (code "27") (name "LCD_DB0") (class "Default")
      (node (ref "SV1") (pin "8") (pinfunction "8_8") (pintype "passive"))
      (node (ref "U1") (pin "38") (pinfunction "P$38_38") (pintype "bidirectional"))
    )
    (net (code "28") (name "LCD_DB1") (class "Default")
      (node (ref "SV1") (pin "9") (pinfunction "9_9") (pintype "passive"))
      (node (ref "U1") (pin "39") (pinfunction "P$39_39") (pintype "bidirectional"))
    )
    (net (code "29") (name "LCD_DB2") (class "Default")
      (node (ref "SV1") (pin "10") (pinfunction "10_10") (pintype "passive"))
      (node (ref "U1") (pin "40") (pinfunction "P$40_40") (pintype "bidirectional"))
    )
    (net (code "30") (name "LCD_DB3") (class "Default")
      (node (ref "SV1") (pin "11") (pinfunction "11_11") (pintype "passive"))
      (node (ref "U1") (pin "41") (pinfunction "P$41_41") (pintype "bidirectional"))
    )
    (net (code "31") (name "LCD_DB4") (class "Default")
      (node (ref "SV1") (pin "12") (pinfunction "12_12") (pintype "passive"))
      (node (ref "U1") (pin "42") (pinfunction "P$42_42") (pintype "bidirectional"))
    )
    (net (code "32") (name "LCD_DB5") (class "Default")
      (node (ref "SV1") (pin "13") (pinfunction "13_13") (pintype "passive"))
      (node (ref "U1") (pin "43") (pinfunction "P$43_43") (pintype "bidirectional"))
    )
    (net (code "33") (name "LCD_DB6") (class "Default")
      (node (ref "SV1") (pin "14") (pinfunction "14_14") (pintype "passive"))
      (node (ref "U1") (pin "44") (pinfunction "P$44_44") (pintype "bidirectional"))
    )
    (net (code "34") (name "LCD_DB7") (class "Default")
      (node (ref "SV1") (pin "15") (pinfunction "15_15") (pintype "passive"))
      (node (ref "U1") (pin "45") (pinfunction "P$45_45") (pintype "bidirectional"))
    )
    (net (code "35") (name "LCD_E") (class "Default")
      (node (ref "SV1") (pin "7") (pinfunction "7_7") (pintype "passive"))
      (node (ref "U1") (pin "37") (pinfunction "P$37_37") (pintype "bidirectional"))
    )
    (net (code "36") (name "LCD_K") (class "Default")
      (node (ref "D1") (pin "A") (pinfunction "A_A") (pintype "passive"))
      (node (ref "Q3") (pin "D") (pinfunction "D_D") (pintype "passive"))
      (node (ref "SV1") (pin "21") (pinfunction "21_21") (pintype "passive"))
    )
    (net (code "37") (name "LCD_PWM") (class "Default")
      (node (ref "R19") (pin "2") (pinfunction "2_2") (pintype "passive"))
      (node (ref "U1") (pin "59") (pinfunction "P$59_59") (pintype "bidirectional"))
    )
    (net (code "38") (name "LCD_RES") (class "Default")
      (node (ref "SV1") (pin "19") (pinfunction "19_19") (pintype "passive"))
      (node (ref "U1") (pin "46") (pinfunction "P$46_46") (pintype "bidirectional"))
    )
    (net (code "39") (name "LCD_RS") (class "Default")
      (node (ref "SV1") (pin "5") (pinfunction "5_5") (pintype "passive"))
      (node (ref "U1") (pin "35") (pinfunction "P$35_35") (pintype "bidirectional"))
    )
    (net (code "40") (name "LCD_RW") (class "Default")
      (node (ref "SV1") (pin "6") (pinfunction "6_6") (pintype "passive"))
      (node (ref "U1") (pin "36") (pinfunction "P$36_36") (pintype "bidirectional"))
    )
    (net (code "41") (name "LED_0") (class "Default")
      (node (ref "R37") (pin "1") (pinfunction "1_1") (pintype "passive"))
      (node (ref "U1") (pin "77") (pinfunction "P$77_77") (pintype "bidirectional"))
    )
    (net (code "42") (name "LED_1") (class "Default")
      (node (ref "R35") (pin "1") (pinfunction "1_1") (pintype "passive"))
      (node (ref "U1") (pin "78") (pinfunction "P$78_78") (pintype "bidirectional"))
    )
    (net (code "43") (name "LED_2") (class "Default")
      (node (ref "R33") (pin "1") (pinfunction "1_1") (pintype "passive"))
      (node (ref "U1") (pin "79") (pinfunction "P$79_79") (pintype "bidirectional"))
    )
    (net (code "44") (name "LED_3") (class "Default")
      (node (ref "R31") (pin "1") (pinfunction "1_1") (pintype "passive"))
      (node (ref "U1") (pin "80") (pinfunction "P$80_80") (pintype "bidirectional"))
    )
    (net (code "45") (name "LED_4") (class "Default")
      (node (ref "R29") (pin "1") (pinfunction "1_1") (pintype "passive"))
      (node (ref "U1") (pin "81") (pinfunction "P$81_81") (pintype "bidirectional"))
    )
    (net (code "46") (name "LED_5") (class "Default")
      (node (ref "R27") (pin "1") (pinfunction "1_1") (pintype "passive"))
      (node (ref "U1") (pin "82") (pinfunction "P$82_82") (pintype "bidirectional"))
    )
    (net (code "47") (name "NRST") (class "Default")
      (node (ref "JP4") (pin "2") (pinfunction "2_2") (pintype "passive"))
      (node (ref "R48") (pin "1") (pinfunction "1_1") (pintype "passive"))
      (node (ref "U1") (pin "14") (pinfunction "P$14_14") (pintype "bidirectional"))
    )
    (net (code "48") (name "Net-(C1-Pad2)") (class "Default")
      (node (ref "C1") (pin "2") (pinfunction "2_2") (pintype "passive"))
      (node (ref "L1") (pin "1") (pinfunction "1_1") (pintype "passive"))
      (node (ref "SV1") (pin "2") (pinfunction "2_2") (pintype "passive"))
    )
    (net (code "49") (name "Net-(C7-Pad2)") (class "Default")
      (node (ref "C7") (pin "2") (pinfunction "2_2") (pintype "passive"))
      (node (ref "L2") (pin "2") (pinfunction "2_2") (pintype "passive"))
      (node (ref "SV2") (pin "10") (pinfunction "10_10") (pintype "passive"))
      (node (ref "SV2") (pin "9") (pinfunction "9_9") (pintype "passive"))
    )
    (net (code "50") (name "Net-(C9-Pad2)") (class "Default")
      (node (ref "C9") (pin "2") (pinfunction "2_2") (pintype "passive"))
      (node (ref "L3") (pin "1") (pinfunction "1_1") (pintype "passive"))
      (node (ref "R49") (pin "2") (pinfunction "2_2") (pintype "passive"))
      (node (ref "SV3") (pin "5") (pinfunction "5_5") (pintype "passive"))
    )
    (net (code "51") (name "Net-(C15-Pad1)") (class "Default")
      (node (ref "C15") (pin "1") (pinfunction "1_1") (pintype "passive"))
      (node (ref "L4") (pin "1") (pinfunction "1_1") (pintype "passive"))
      (node (ref "SV4") (pin "10") (pinfunction "10_10") (pintype "passive"))
      (node (ref "SV4") (pin "6") (pinfunction "6_6") (pintype "passive"))
      (node (ref "SV4") (pin "8") (pinfunction "8_8") (pintype "passive"))
    )
    (net (code "52") (name "Net-(C19-Pad2)") (class "Default")
      (node (ref "C19") (pin "2") (pinfunction "2_2") (pintype "passive"))
      (node (ref "L5") (pin "1") (pinfunction "1_1") (pintype "passive"))
      (node (ref "SV4") (pin "5") (pinfunction "5_5") (pintype "passive"))
      (node (ref "SV4") (pin "7") (pinfunction "7_7") (pintype "passive"))
      (node (ref "SV4") (pin "9") (pinfunction "9_9") (pintype "passive"))
    )
    (net (code "53") (name "Net-(C20-Pad2)") (class "Default")
      (node (ref "C20") (pin "2") (pinfunction "2_2") (pintype "passive"))
      (node (ref "L6") (pin "1") (pinfunction "1_1") (pintype "passive"))
      (node (ref "SV5") (pin "10") (pinfunction "10_10") (pintype "passive"))
      (node (ref "SV5") (pin "9") (pinfunction "9_9") (pintype "passive"))
    )
    (net (code "54") (name "Net-(JP3-Pad1)") (class "Default")
      (node (ref "JP3") (pin "1") (pinfunction "1_1") (pintype "passive"))
      (node (ref "R28") (pin "2") (pinfunction "2_2") (pintype "passive"))
    )
    (net (code "55") (name "Net-(JP3-Pad3)") (class "Default")
      (node (ref "JP3") (pin "3") (pinfunction "3_3") (pintype "passive"))
      (node (ref "R30") (pin "2") (pinfunction "2_2") (pintype "passive"))
    )
    (net (code "56") (name "Net-(JP3-Pad5)") (class "Default")
      (node (ref "JP3") (pin "5") (pinfunction "5_5") (pintype "passive"))
      (node (ref "R32") (pin "2") (pinfunction "2_2") (pintype "passive"))
    )
    (net (code "57") (name "Net-(JP3-Pad7)") (class "Default")
      (node (ref "JP3") (pin "7") (pinfunction "7_7") (pintype "passive"))
      (node (ref "R34") (pin "2") (pinfunction "2_2") (pintype "passive"))
    )
    (net (code "58") (name "Net-(JP3-Pad9)") (class "Default")
      (node (ref "JP3") (pin "9") (pinfunction "9_9") (pintype "passive"))
      (node (ref "R36") (pin "2") (pinfunction "2_2") (pintype "passive"))
    )
    (net (code "59") (name "Net-(JP3-Pad11)") (class "Default")
      (node (ref "JP3") (pin "11") (pinfunction "11_11") (pintype "passive"))
      (node (ref "R38") (pin "2") (pinfunction "2_2") (pintype "passive"))
    )
    (net (code "60") (name "Net-(JP7-Pad1)") (class "Default")
      (node (ref "JP7") (pin "1") (pinfunction "1_1") (pintype "passive"))
      (node (ref "R44") (pin "1") (pinfunction "1_1") (pintype "passive"))
      (node (ref "R47") (pin "1") (pinfunction "1_1") (pintype "passive"))
    )
    (net (code "61") (name "Net-(JP7-Pad3)") (class "Default")
      (node (ref "JP7") (pin "3") (pinfunction "3_3") (pintype "passive"))
      (node (ref "R45") (pin "1") (pinfunction "1_1") (pintype "passive"))
      (node (ref "R46") (pin "1") (pinfunction "1_1") (pintype "passive"))
    )
    (net (code "62") (name "Net-(Q3-PadG)") (class "Default")
      (node (ref "Q3") (pin "G") (pinfunction "G_G") (pintype "passive"))
      (node (ref "R19") (pin "1") (pinfunction "1_1") (pintype "passive"))
      (node (ref "R20") (pin "1") (pinfunction "1_1") (pintype "passive"))
    )
    (net (code "63") (name "Net-(T3-B)") (class "Default")
      (node (ref "R27") (pin "2") (pinfunction "2_2") (pintype "passive"))
      (node (ref "T3") (pin "1") (pinfunction "B_1") (pintype "passive"))
    )
    (net (code "64") (name "Net-(T3-C)") (class "Default")
      (node (ref "R28") (pin "1") (pinfunction "1_1") (pintype "passive"))
      (node (ref "T3") (pin "3") (pinfunction "C_3") (pintype "passive"))
    )
    (net (code "65") (name "Net-(T4-B)") (class "Default")
      (node (ref "R29") (pin "2") (pinfunction "2_2") (pintype "passive"))
      (node (ref "T4") (pin "1") (pinfunction "B_1") (pintype "passive"))
    )
    (net (code "66") (name "Net-(T4-C)") (class "Default")
      (node (ref "R30") (pin "1") (pinfunction "1_1") (pintype "passive"))
      (node (ref "T4") (pin "3") (pinfunction "C_3") (pintype "passive"))
    )
    (net (code "67") (name "Net-(T5-B)") (class "Default")
      (node (ref "R31") (pin "2") (pinfunction "2_2") (pintype "passive"))
      (node (ref "T5") (pin "1") (pinfunction "B_1") (pintype "passive"))
    )
    (net (code "68") (name "Net-(T5-C)") (class "Default")
      (node (ref "R32") (pin "1") (pinfunction "1_1") (pintype "passive"))
      (node (ref "T5") (pin "3") (pinfunction "C_3") (pintype "passive"))
    )
    (net (code "69") (name "Net-(T6-B)") (class "Default")
      (node (ref "R33") (pin "2") (pinfunction "2_2") (pintype "passive"))
      (node (ref "T6") (pin "1") (pinfunction "B_1") (pintype "passive"))
    )
    (net (code "70") (name "Net-(T6-C)") (class "Default")
      (node (ref "R34") (pin "1") (pinfunction "1_1") (pintype "passive"))
      (node (ref "T6") (pin "3") (pinfunction "C_3") (pintype "passive"))
    )
    (net (code "71") (name "Net-(T7-B)") (class "Default")
      (node (ref "R35") (pin "2") (pinfunction "2_2") (pintype "passive"))
      (node (ref "T7") (pin "1") (pinfunction "B_1") (pintype "passive"))
    )
    (net (code "72") (name "Net-(T7-C)") (class "Default")
      (node (ref "R36") (pin "1") (pinfunction "1_1") (pintype "passive"))
      (node (ref "T7") (pin "3") (pinfunction "C_3") (pintype "passive"))
    )
    (net (code "73") (name "Net-(T8-B)") (class "Default")
      (node (ref "R37") (pin "2") (pinfunction "2_2") (pintype "passive"))
      (node (ref "T8") (pin "1") (pinfunction "B_1") (pintype "passive"))
    )
    (net (code "74") (name "Net-(T8-C)") (class "Default")
      (node (ref "R38") (pin "1") (pinfunction "1_1") (pintype "passive"))
      (node (ref "T8") (pin "3") (pinfunction "C_3") (pintype "passive"))
    )
    (net (code "75") (name "Net-(U1-P$1)") (class "Default")
      (node (ref "TP7") (pin "TP") (pinfunction "TP_TP") (pintype "input"))
      (node (ref "U1") (pin "1") (pinfunction "P$1_1") (pintype "bidirectional"))
    )
    (net (code "76") (name "Net-(U1-P$2)") (class "Default")
      (node (ref "TP8") (pin "TP") (pinfunction "TP_TP") (pintype "input"))
      (node (ref "U1") (pin "2") (pinfunction "P$2_2") (pintype "bidirectional"))
    )
    (net (code "77") (name "Net-(U1-P$48)") (class "Default")
      (node (ref "C31") (pin "1") (pinfunction "1_1") (pintype "passive"))
      (node (ref "U1") (pin "48") (pinfunction "P$48_48") (pintype "bidirectional"))
    )
    (net (code "78") (name "Net-(U1-P$73)") (class "Default")
      (node (ref "C33") (pin "1") (pinfunction "1_1") (pintype "passive"))
      (node (ref "U1") (pin "73") (pinfunction "P$73_73") (pintype "bidirectional"))
    )
    (net (code "79") (name "OSC_IN") (class "Default")
      (node (ref "OS1") (pin "3") (pinfunction "OUT_3") (pintype "output"))
      (node (ref "U1") (pin "12") (pinfunction "P$12_12") (pintype "bidirectional"))
    )
    (net (code "80") (name "PWM_FAN_L") (class "Default")
      (node (ref "U1") (pin "60") (pinfunction "P$60_60") (pintype "bidirectional"))
    )
    (net (code "81") (name "PWM_FAN_R") (class "Default")
      (node (ref "U1") (pin "61") (pinfunction "P$61_61") (pintype "bidirectional"))
    )
    (net (code "82") (name "RX_CS") (class "Default")
      (node (ref "SV2") (pin "5") (pinfunction "5_5") (pintype "passive"))
      (node (ref "U1") (pin "32") (pinfunction "P$32_32") (pintype "bidirectional"))
    )
    (net (code "83") (name "RX_MISO") (class "Default")
      (node (ref "SV2") (pin "3") (pinfunction "3_3") (pintype "passive"))
      (node (ref "U1") (pin "30") (pinfunction "P$30_30") (pintype "bidirectional"))
    )
    (net (code "84") (name "RX_MOSI") (class "Default")
      (node (ref "SV2") (pin "6") (pinfunction "6_6") (pintype "passive"))
      (node (ref "U1") (pin "31") (pinfunction "P$31_31") (pintype "bidirectional"))
    )
    (net (code "85") (name "RX_NIRQ") (class "Default")
      (node (ref "SV2") (pin "1") (pinfunction "1_1") (pintype "passive"))
      (node (ref "U1") (pin "33") (pinfunction "P$33_33") (pintype "bidirectional"))
    )
    (net (code "86") (name "RX_SCK") (class "Default")
      (node (ref "SV2") (pin "4") (pinfunction "4_4") (pintype "passive"))
      (node (ref "U1") (pin "29") (pinfunction "P$29_29") (pintype "bidirectional"))
    )
    (net (code "87") (name "RX_SDN") (class "Default")
      (node (ref "SV2") (pin "8") (pinfunction "8_8") (pintype "passive"))
      (node (ref "U1") (pin "34") (pinfunction "P$34_34") (pintype "bidirectional"))
    )
    (net (code "88") (name "SWCLK") (class "Default")
      (node (ref "JP4") (pin "3") (pinfunction "3_3") (pintype "passive"))
      (node (ref "U1") (pin "76") (pinfunction "P$76_76") (pintype "bidirectional"))
    )
    (net (code "89") (name "SWDIO") (class "Default")
      (node (ref "JP4") (pin "4") (pinfunction "4_4") (pintype "passive"))
      (node (ref "U1") (pin "72") (pinfunction "P$72_72") (pintype "bidirectional"))
    )
    (net (code "90") (name "TAMPER") (class "Default")
      (node (ref "C35") (pin "1") (pinfunction "1_1") (pintype "passive"))
      (node (ref "JP6") (pin "1") (pinfunction "1_1") (pintype "passive"))
      (node (ref "R43") (pin "2") (pinfunction "2_2") (pintype "passive"))
      (node (ref "U1") (pin "5") (pinfunction "P$5_5") (pintype "bidirectional"))
    )
    (net (code "91") (name "TX_CS") (class "Default")
      (node (ref "SV5") (pin "5") (pinfunction "5_5") (pintype "passive"))
      (node (ref "U1") (pin "55") (pinfunction "P$55_55") (pintype "bidirectional"))
    )
    (net (code "92") (name "TX_MISO") (class "Default")
      (node (ref "SV5") (pin "3") (pinfunction "3_3") (pintype "passive"))
      (node (ref "U1") (pin "53") (pinfunction "P$53_53") (pintype "bidirectional"))
    )
    (net (code "93") (name "TX_MOSI") (class "Default")
      (node (ref "SV5") (pin "6") (pinfunction "6_6") (pintype "passive"))
      (node (ref "U1") (pin "54") (pinfunction "P$54_54") (pintype "bidirectional"))
    )
    (net (code "94") (name "TX_NIRQ") (class "Default")
      (node (ref "SV5") (pin "1") (pinfunction "1_1") (pintype "passive"))
      (node (ref "U1") (pin "56") (pinfunction "P$56_56") (pintype "bidirectional"))
    )
    (net (code "95") (name "TX_SCK") (class "Default")
      (node (ref "SV5") (pin "4") (pinfunction "4_4") (pintype "passive"))
      (node (ref "U1") (pin "52") (pinfunction "P$52_52") (pintype "bidirectional"))
    )
    (net (code "96") (name "TX_SDN") (class "Default")
      (node (ref "SV5") (pin "8") (pinfunction "8_8") (pintype "passive"))
      (node (ref "U1") (pin "51") (pinfunction "P$51_51") (pintype "bidirectional"))
    )
    (net (code "97") (name "VDDA") (class "Default")
      (node (ref "C23") (pin "1") (pinfunction "1_1") (pintype "passive"))
      (node (ref "L8") (pin "2") (pinfunction "2_2") (pintype "passive"))
      (node (ref "U1") (pin "21") (pinfunction "P$21_21") (pintype "bidirectional"))
    )
    (net (code "98") (name "VREF") (class "Default")
      (node (ref "C24") (pin "1") (pinfunction "1_1") (pintype "passive"))
      (node (ref "L7") (pin "2") (pinfunction "2_2") (pintype "passive"))
      (node (ref "U1") (pin "20") (pinfunction "P$20_20") (pintype "bidirectional"))
    )
    (net (code "99") (name "unconnected-(IC3C-O-Pad8)") (class "Default")
      (node (ref "IC3") (pin "8") (pinfunction "O_8") (pintype "output"))
    )
    (net (code "100") (name "unconnected-(IC3D-O-Pad11)") (class "Default")
      (node (ref "IC3") (pin "11") (pinfunction "O_11") (pintype "output"))
    )
    (net (code "101") (name "unconnected-(OS1-CON-Pad1)") (class "Default")
      (node (ref "OS1") (pin "1") (pinfunction "CON_1") (pintype "input"))
    )
    (net (code "102") (name "unconnected-(SV1-Pad4)") (class "Default")
      (node (ref "SV1") (pin "4") (pinfunction "4_4") (pintype "passive"))
    )
    (net (code "103") (name "unconnected-(SV1-Pad22)") (class "Default")
      (node (ref "SV1") (pin "22") (pinfunction "22_22") (pintype "passive"))
    )
    (net (code "104") (name "unconnected-(SV1-Pad23)") (class "Default")
      (node (ref "SV1") (pin "23") (pinfunction "23_23") (pintype "passive"))
    )
    (net (code "105") (name "unconnected-(SV1-Pad24)") (class "Default")
      (node (ref "SV1") (pin "24") (pinfunction "24_24") (pintype "passive"))
    )
    (net (code "106") (name "unconnected-(SV1-Pad25)") (class "Default")
      (node (ref "SV1") (pin "25") (pinfunction "25_25") (pintype "passive"))
    )
    (net (code "107") (name "unconnected-(SV1-Pad26)") (class "Default")
      (node (ref "SV1") (pin "26") (pinfunction "26_26") (pintype "passive"))
    )
    (net (code "108") (name "unconnected-(SV3-Pad1)") (class "Default")
      (node (ref "SV3") (pin "1") (pinfunction "1_1") (pintype "passive"))
    )
    (net (code "109") (name "unconnected-(SV4-Pad3)") (class "Default")
      (node (ref "SV4") (pin "3") (pinfunction "3_3") (pintype "passive"))
    )
    (net (code "110") (name "unconnected-(U1-P$3-Pad3)") (class "Default")
      (node (ref "U1") (pin "3") (pinfunction "P$3_3") (pintype "bidirectional"))
    )
    (net (code "111") (name "unconnected-(U1-P$4-Pad4)") (class "Default")
      (node (ref "U1") (pin "4") (pinfunction "P$4_4") (pintype "bidirectional"))
    )
    (net (code "112") (name "unconnected-(U1-P$7-Pad7)") (class "Default")
      (node (ref "U1") (pin "7") (pinfunction "P$7_7") (pintype "bidirectional"))
    )
    (net (code "113") (name "unconnected-(U1-P$8-Pad8)") (class "Default")
      (node (ref "U1") (pin "8") (pinfunction "P$8_8") (pintype "bidirectional"))
    )
    (net (code "114") (name "unconnected-(U1-P$9-Pad9)") (class "Default")
      (node (ref "U1") (pin "9") (pinfunction "P$9_9") (pintype "bidirectional"))
    )
    (net (code "115") (name "unconnected-(U1-P$13-Pad13)") (class "Default")
      (node (ref "U1") (pin "13") (pinfunction "P$13_13") (pintype "bidirectional"))
    )
    (net (code "116") (name "unconnected-(U1-P$18-Pad18)") (class "Default")
      (node (ref "U1") (pin "18") (pinfunction "P$18_18") (pintype "bidirectional"))
    )
    (net (code "117") (name "unconnected-(U1-P$47-Pad47)") (class "Default")
      (node (ref "U1") (pin "47") (pinfunction "P$47_47") (pintype "bidirectional"))
    )
    (net (code "118") (name "unconnected-(U1-P$57-Pad57)") (class "Default")
      (node (ref "U1") (pin "57") (pinfunction "P$57_57") (pintype "bidirectional"))
    )
    (net (code "119") (name "unconnected-(U1-P$58-Pad58)") (class "Default")
      (node (ref "U1") (pin "58") (pinfunction "P$58_58") (pintype "bidirectional"))
    )
    (net (code "120") (name "unconnected-(U1-P$62-Pad62)") (class "Default")
      (node (ref "U1") (pin "62") (pinfunction "P$62_62") (pintype "bidirectional"))
    )
    (net (code "121") (name "unconnected-(U1-P$63-Pad63)") (class "Default")
      (node (ref "U1") (pin "63") (pinfunction "P$63_63") (pintype "bidirectional"))
    )
    (net (code "122") (name "unconnected-(U1-P$64-Pad64)") (class "Default")
      (node (ref "U1") (pin "64") (pinfunction "P$64_64") (pintype "bidirectional"))
    )
    (net (code "123") (name "unconnected-(U1-P$65-Pad65)") (class "Default")
      (node (ref "U1") (pin "65") (pinfunction "P$65_65") (pintype "bidirectional"))
    )
    (net (code "124") (name "unconnected-(U1-P$66-Pad66)") (class "Default")
      (node (ref "U1") (pin "66") (pinfunction "P$66_66") (pintype "bidirectional"))
    )
    (net (code "125") (name "unconnected-(U1-P$67-Pad67)") (class "Default")
      (node (ref "U1") (pin "67") (pinfunction "P$67_67") (pintype "bidirectional"))
    )
    (net (code "126") (name "unconnected-(U1-P$70-Pad70)") (class "Default")
      (node (ref "U1") (pin "70") (pinfunction "P$70_70") (pintype "bidirectional"))
    )
    (net (code "127") (name "unconnected-(U1-P$71-Pad71)") (class "Default")
      (node (ref "U1") (pin "71") (pinfunction "P$71_71") (pintype "bidirectional"))
    )
    (net (code "128") (name "unconnected-(U1-P$86-Pad86)") (class "Default")
      (node (ref "U1") (pin "86") (pinfunction "P$86_86") (pintype "bidirectional"))
    )
    (net (code "129") (name "unconnected-(U1-P$87-Pad87)") (class "Default")
      (node (ref "U1") (pin "87") (pinfunction "P$87_87") (pintype "bidirectional"))
    )
    (net (code "130") (name "unconnected-(U1-P$89-Pad89)") (class "Default")
      (node (ref "U1") (pin "89") (pinfunction "P$89_89") (pintype "bidirectional"))
    )
    (net (code "131") (name "unconnected-(U1-P$92-Pad92)") (class "Default")
      (node (ref "U1") (pin "92") (pinfunction "P$92_92") (pintype "bidirectional"))
    )
    (net (code "132") (name "unconnected-(U1-P$93-Pad93)") (class "Default")
      (node (ref "U1") (pin "93") (pinfunction "P$93_93") (pintype "bidirectional"))
    )
    (net (code "133") (name "unconnected-(U1-P$95-Pad95)") (class "Default")
      (node (ref "U1") (pin "95") (pinfunction "P$95_95") (pintype "bidirectional"))
    )
    (net (code "134") (name "unconnected-(U1-P$96-Pad96)") (class "Default")
      (node (ref "U1") (pin "96") (pinfunction "P$96_96") (pintype "bidirectional"))
    )
  )
)
